# board.net
KiCad netlist of a schematic drawn in EAGLE
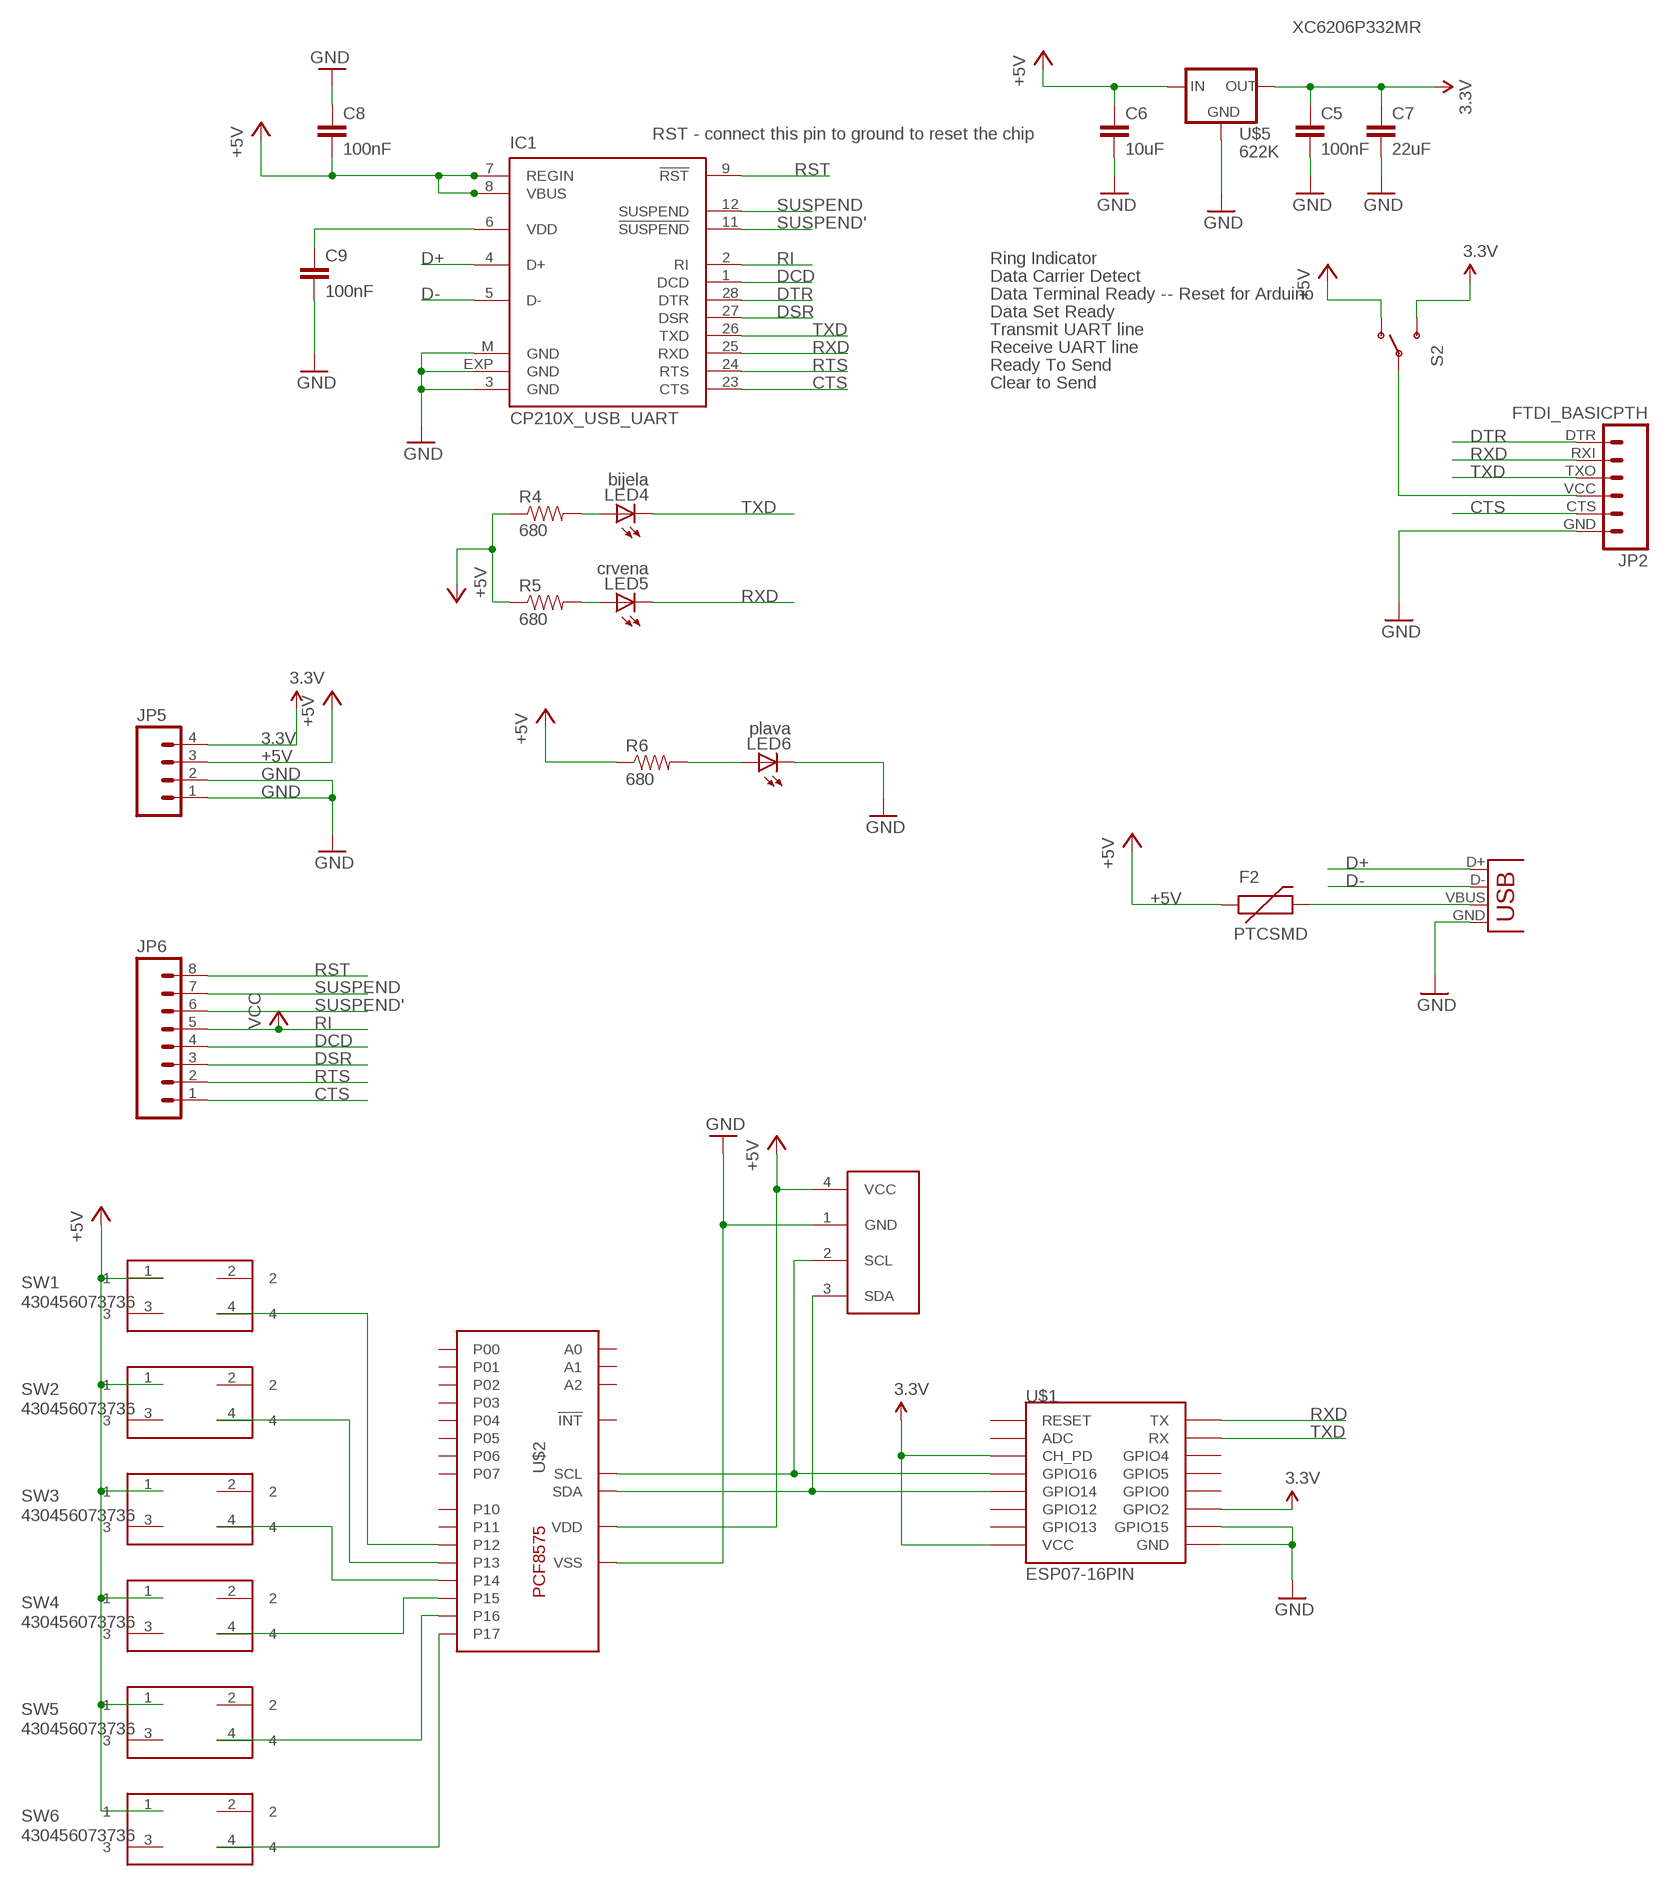
[diagram p0: schematic, sheet 1]

(export (version "E")
  (design (tool "Eeschema 10.0.6"))
  (components
    (comp (ref "C5")
      (value "100nF")
      (footprint "eagle-import:0603-CAP")
      (libsource (lib "eagle-import") (part "CAP0603-CAP"))
    )
    (comp (ref "C6")
      (value "10uF")
      (footprint "eagle-import:C3216")
      (libsource (lib "eagle-import") (part "C-EUC3216"))
    )
    (comp (ref "C7")
      (value "22uF")
      (footprint "eagle-import:C3216")
      (libsource (lib "eagle-import") (part "C-EUC3216"))
    )
    (comp (ref "C8")
      (value "100nF")
      (footprint "eagle-import:0603-CAP")
      (libsource (lib "eagle-import") (part "CAP0603-CAP"))
    )
    (comp (ref "C9")
      (value "100nF")
      (footprint "eagle-import:0603-CAP")
      (libsource (lib "eagle-import") (part "CAP0603-CAP"))
    )
    (comp (ref "F2")
      (value "PTCSMD")
      (footprint "eagle-import:PTC-1206")
      (libsource (lib "eagle-import") (part "PTCSMD"))
    )
    (comp (ref "IC1")
      (value "CP210X_USB_UART")
      (footprint "eagle-import:MLP28")
      (libsource (lib "eagle-import") (part "CP210X_USB_UART"))
    )
    (comp (ref "JP2")
      (value "FTDI_BASICPTH")
      (footprint "eagle-import:FTDI_BASIC")
      (libsource (lib "eagle-import") (part "FTDI_BASICPTH"))
    )
    (comp (ref "JP5")
      (value "M04PTH")
      (footprint "eagle-import:1X04")
      (libsource (lib "eagle-import") (part "M04PTH"))
    )
    (comp (ref "JP6")
      (value "M081X08")
      (footprint "eagle-import:1X08")
      (libsource (lib "eagle-import") (part "M081X08"))
    )
    (comp (ref "LED4")
      (value "bijela")
      (footprint "eagle-import:CHIP-LED0805")
      (libsource (lib "eagle-import") (part "LEDCHIP-LED0805"))
    )
    (comp (ref "LED5")
      (value "crvena")
      (footprint "eagle-import:CHIP-LED0805")
      (libsource (lib "eagle-import") (part "LEDCHIP-LED0805"))
    )
    (comp (ref "LED6")
      (value "plava")
      (footprint "eagle-import:CHIP-LED0805")
      (libsource (lib "eagle-import") (part "LEDCHIP-LED0805"))
    )
    (comp (ref "R4")
      (value "680")
      (footprint "eagle-import:0603-RES")
      (libsource (lib "eagle-import") (part "RESISTOR0603-RES"))
    )
    (comp (ref "R5")
      (value "680")
      (footprint "eagle-import:0603-RES")
      (libsource (lib "eagle-import") (part "RESISTOR0603-RES"))
    )
    (comp (ref "R6")
      (value "680")
      (footprint "eagle-import:0603-RES")
      (libsource (lib "eagle-import") (part "RESISTOR0603-RES"))
    )
    (comp (ref "S2")
      (value "SWITCH-SPST-SMD-A")
      (footprint "eagle-import:SWITCH-SPST-SMD-A")
      (libsource (lib "eagle-import") (part "SWITCH-SPST-SMD-A"))
    )
    (comp (ref "SW1")
      (value "430456073736")
      (footprint "eagle-import:430456073736")
      (libsource (lib "eagle-import") (part "430456073736"))
    )
    (comp (ref "SW2")
      (value "430456073736")
      (footprint "eagle-import:430456073736")
      (libsource (lib "eagle-import") (part "430456073736"))
    )
    (comp (ref "SW3")
      (value "430456073736")
      (footprint "eagle-import:430456073736")
      (libsource (lib "eagle-import") (part "430456073736"))
    )
    (comp (ref "SW4")
      (value "430456073736")
      (footprint "eagle-import:430456073736")
      (libsource (lib "eagle-import") (part "430456073736"))
    )
    (comp (ref "SW5")
      (value "430456073736")
      (footprint "eagle-import:430456073736")
      (libsource (lib "eagle-import") (part "430456073736"))
    )
    (comp (ref "SW6")
      (value "430456073736")
      (footprint "eagle-import:430456073736")
      (libsource (lib "eagle-import") (part "430456073736"))
    )
    (comp (ref "U$1")
      (value "ESP07-16PIN")
      (footprint "eagle-import:ESP07-16PIN")
      (libsource (lib "eagle-import") (part "ESP07-16PIN"))
    )
    (comp (ref "U$2")
      (value "PCF8575C")
      (footprint "eagle-import:SOP24")
      (libsource (lib "eagle-import") (part "PCF8575C"))
    )
    (comp (ref "U$3")
      (value "I2C_OLED")
      (footprint "eagle-import:I2C_OLED_PACKAGE")
      (libsource (lib "eagle-import") (part "I2C_OLED"))
    )
    (comp (ref "U$5")
      (value "622K")
      (footprint "eagle-import:662K")
      (libsource (lib "eagle-import") (part "622K"))
    )
    (comp (ref "X2")
      (value "USB-MICROB")
      (footprint "eagle-import:USB-MICROB")
      (libsource (lib "eagle-import") (part "USB-MICROB"))
    )
  )
  (nets
    (net (code "1") (name "+5V") (class "Default")
      (node (ref "C6") (pin "1") (pinfunction "1_1") (pintype "passive"))
      (node (ref "C8") (pin "2") (pinfunction "2_2") (pintype "passive"))
      (node (ref "F2") (pin "1") (pinfunction "1_1") (pintype "bidirectional"))
      (node (ref "IC1") (pin "7") (pinfunction "REGIN_7") (pintype "passive"))
      (node (ref "IC1") (pin "8") (pinfunction "VBUS_8") (pintype "input"))
      (node (ref "JP5") (pin "3") (pinfunction "3_3") (pintype "passive"))
      (node (ref "R4") (pin "1") (pinfunction "1_1") (pintype "passive"))
      (node (ref "R5") (pin "1") (pinfunction "1_1") (pintype "passive"))
      (node (ref "R6") (pin "1") (pinfunction "1_1") (pintype "passive"))
      (node (ref "S2") (pin "1") (pinfunction "O_1") (pintype "passive"))
      (node (ref "SW1") (pin "1") (pinfunction "1_1") (pintype "bidirectional"))
      (node (ref "SW2") (pin "1") (pinfunction "1_1") (pintype "bidirectional"))
      (node (ref "SW3") (pin "1") (pinfunction "1_1") (pintype "bidirectional"))
      (node (ref "SW4") (pin "1") (pinfunction "1_1") (pintype "bidirectional"))
      (node (ref "SW5") (pin "1") (pinfunction "1_1") (pintype "bidirectional"))
      (node (ref "SW6") (pin "1") (pinfunction "1_1") (pintype "bidirectional"))
      (node (ref "U$2") (pin "P$24") (pinfunction "VDD_P$24") (pintype "power_in"))
      (node (ref "U$3") (pin "4") (pinfunction "VCC_4") (pintype "bidirectional"))
      (node (ref "U$5") (pin "IN") (pinfunction "IN_IN") (pintype "input"))
    )
    (net (code "2") (name "/CTS") (class "Default")
      (node (ref "IC1") (pin "23") (pinfunction "CTS_23") (pintype "input"))
      (node (ref "JP2") (pin "CTS") (pinfunction "5_CTS") (pintype "passive"))
      (node (ref "JP6") (pin "1") (pinfunction "1_1") (pintype "passive"))
    )
    (net (code "3") (name "/D+") (class "Default")
      (node (ref "IC1") (pin "4") (pinfunction "D+_4") (pintype "bidirectional"))
      (node (ref "X2") (pin "D+") (pinfunction "D+_D+") (pintype "bidirectional"))
    )
    (net (code "4") (name "/D-") (class "Default")
      (node (ref "IC1") (pin "5") (pinfunction "D-_5") (pintype "bidirectional"))
      (node (ref "X2") (pin "D-") (pinfunction "D-_D-") (pintype "bidirectional"))
    )
    (net (code "5") (name "/DCD") (class "Default")
      (node (ref "IC1") (pin "1") (pinfunction "DCD_1") (pintype "input"))
      (node (ref "JP6") (pin "4") (pinfunction "4_4") (pintype "passive"))
    )
    (net (code "6") (name "/DSR") (class "Default")
      (node (ref "IC1") (pin "27") (pinfunction "DSR_27") (pintype "input"))
      (node (ref "JP6") (pin "3") (pinfunction "3_3") (pintype "passive"))
    )
    (net (code "7") (name "/DTR") (class "Default")
      (node (ref "IC1") (pin "28") (pinfunction "DTR_28") (pintype "output"))
      (node (ref "JP2") (pin "DTR") (pinfunction "1_DTR") (pintype "passive"))
    )
    (net (code "8") (name "/RST") (class "Default")
      (node (ref "IC1") (pin "9") (pinfunction "~{RST}_9") (pintype "bidirectional"))
      (node (ref "JP6") (pin "8") (pinfunction "8_8") (pintype "passive"))
    )
    (net (code "9") (name "/RTS") (class "Default")
      (node (ref "IC1") (pin "24") (pinfunction "RTS_24") (pintype "output"))
      (node (ref "JP6") (pin "2") (pinfunction "2_2") (pintype "passive"))
    )
    (net (code "10") (name "/RXD") (class "Default")
      (node (ref "IC1") (pin "25") (pinfunction "RXD_25") (pintype "input"))
      (node (ref "JP2") (pin "RXI") (pinfunction "2_RXI") (pintype "passive"))
      (node (ref "LED5") (pin "C") (pinfunction "C_C") (pintype "passive"))
      (node (ref "U$1") (pin "TX") (pinfunction "TX_TX") (pintype "bidirectional"))
    )
    (net (code "11") (name "/SUSPEND") (class "Default")
      (node (ref "IC1") (pin "12") (pinfunction "SUSPEND_12") (pintype "output"))
      (node (ref "JP6") (pin "7") (pinfunction "7_7") (pintype "passive"))
    )
    (net (code "12") (name "/SUSPEND'") (class "Default")
      (node (ref "IC1") (pin "11") (pinfunction "~{SUSPEND}_11") (pintype "output"))
      (node (ref "JP6") (pin "6") (pinfunction "6_6") (pintype "passive"))
    )
    (net (code "13") (name "/TXD") (class "Default")
      (node (ref "IC1") (pin "26") (pinfunction "TXD_26") (pintype "output"))
      (node (ref "JP2") (pin "TXO") (pinfunction "3_TXO") (pintype "passive"))
      (node (ref "LED4") (pin "C") (pinfunction "C_C") (pintype "passive"))
      (node (ref "U$1") (pin "RX") (pinfunction "RX_RX") (pintype "bidirectional"))
    )
    (net (code "14") (name "3.3V") (class "Default")
      (node (ref "C5") (pin "1") (pinfunction "1_1") (pintype "passive"))
      (node (ref "C7") (pin "1") (pinfunction "1_1") (pintype "passive"))
      (node (ref "JP5") (pin "4") (pinfunction "4_4") (pintype "passive"))
      (node (ref "S2") (pin "3") (pinfunction "S_3") (pintype "passive"))
      (node (ref "U$1") (pin "CH_PD") (pinfunction "CH_PD_CH_PD") (pintype "bidirectional"))
      (node (ref "U$1") (pin "GPIO2") (pinfunction "GPIO2_GPIO2") (pintype "bidirectional"))
      (node (ref "U$1") (pin "VCC") (pinfunction "VCC_VCC") (pintype "bidirectional"))
      (node (ref "U$5") (pin "OUT") (pinfunction "OUT_OUT") (pintype "output"))
    )
    (net (code "15") (name "GND") (class "Default")
      (node (ref "C5") (pin "2") (pinfunction "2_2") (pintype "passive"))
      (node (ref "C6") (pin "2") (pinfunction "2_2") (pintype "passive"))
      (node (ref "C7") (pin "2") (pinfunction "2_2") (pintype "passive"))
      (node (ref "C8") (pin "1") (pinfunction "1_1") (pintype "passive"))
      (node (ref "C9") (pin "2") (pinfunction "2_2") (pintype "passive"))
      (node (ref "IC1") (pin "3") (pinfunction "GND_3") (pintype "power_in"))
      (node (ref "IC1") (pin "EXP") (pinfunction "GND_EXP") (pintype "power_in"))
      (node (ref "IC1") (pin "M") (pinfunction "GND_M") (pintype "power_in"))
      (node (ref "JP2") (pin "GND") (pinfunction "6_GND") (pintype "passive"))
      (node (ref "JP5") (pin "1") (pinfunction "1_1") (pintype "passive"))
      (node (ref "JP5") (pin "2") (pinfunction "2_2") (pintype "passive"))
      (node (ref "LED6") (pin "C") (pinfunction "C_C") (pintype "passive"))
      (node (ref "U$1") (pin "GND") (pinfunction "GND_GND") (pintype "bidirectional"))
      (node (ref "U$1") (pin "GPIO15") (pinfunction "GPIO15_GPIO15") (pintype "bidirectional"))
      (node (ref "U$2") (pin "P$12") (pinfunction "VSS_P$12") (pintype "power_in"))
      (node (ref "U$3") (pin "1") (pinfunction "GND_1") (pintype "bidirectional"))
      (node (ref "U$5") (pin "GND") (pinfunction "GND_GND") (pintype "input"))
      (node (ref "X2") (pin "GND") (pinfunction "GND_GND") (pintype "bidirectional"))
    )
    (net (code "16") (name "Net-(F2-Pad2)") (class "Default")
      (node (ref "F2") (pin "2") (pinfunction "2_2") (pintype "bidirectional"))
      (node (ref "X2") (pin "VBUS") (pinfunction "VBUS_VBUS") (pintype "bidirectional"))
    )
    (net (code "17") (name "Net-(IC1-VDD)") (class "Default")
      (node (ref "C9") (pin "1") (pinfunction "1_1") (pintype "passive"))
      (node (ref "IC1") (pin "6") (pinfunction "VDD_6") (pintype "power_in"))
    )
    (net (code "18") (name "Net-(JP2-4)") (class "Default")
      (node (ref "JP2") (pin "VCC") (pinfunction "4_VCC") (pintype "passive"))
      (node (ref "S2") (pin "2") (pinfunction "P_2") (pintype "passive"))
    )
    (net (code "19") (name "Net-(LED4-PadA)") (class "Default")
      (node (ref "LED4") (pin "A") (pinfunction "A_A") (pintype "passive"))
      (node (ref "R4") (pin "2") (pinfunction "2_2") (pintype "passive"))
    )
    (net (code "20") (name "Net-(LED5-PadA)") (class "Default")
      (node (ref "LED5") (pin "A") (pinfunction "A_A") (pintype "passive"))
      (node (ref "R5") (pin "2") (pinfunction "2_2") (pintype "passive"))
    )
    (net (code "21") (name "Net-(LED6-PadA)") (class "Default")
      (node (ref "LED6") (pin "A") (pinfunction "A_A") (pintype "passive"))
      (node (ref "R6") (pin "2") (pinfunction "2_2") (pintype "passive"))
    )
    (net (code "22") (name "Net-(U$2-P12)") (class "Default")
      (node (ref "SW1") (pin "4") (pinfunction "4_4") (pintype "bidirectional"))
      (node (ref "U$2") (pin "P$15") (pinfunction "P12_P$15") (pintype "bidirectional"))
    )
    (net (code "23") (name "Net-(U$2-P13)") (class "Default")
      (node (ref "SW2") (pin "4") (pinfunction "4_4") (pintype "bidirectional"))
      (node (ref "U$2") (pin "P$16") (pinfunction "P13_P$16") (pintype "bidirectional"))
    )
    (net (code "24") (name "Net-(U$2-P14)") (class "Default")
      (node (ref "SW3") (pin "4") (pinfunction "4_4") (pintype "bidirectional"))
      (node (ref "U$2") (pin "P$17") (pinfunction "P14_P$17") (pintype "bidirectional"))
    )
    (net (code "25") (name "Net-(U$2-P15)") (class "Default")
      (node (ref "SW4") (pin "4") (pinfunction "4_4") (pintype "bidirectional"))
      (node (ref "U$2") (pin "P$18") (pinfunction "P15_P$18") (pintype "bidirectional"))
    )
    (net (code "26") (name "Net-(U$2-P16)") (class "Default")
      (node (ref "SW5") (pin "4") (pinfunction "4_4") (pintype "bidirectional"))
      (node (ref "U$2") (pin "P$19") (pinfunction "P16_P$19") (pintype "bidirectional"))
    )
    (net (code "27") (name "Net-(U$2-P17)") (class "Default")
      (node (ref "SW6") (pin "4") (pinfunction "4_4") (pintype "bidirectional"))
      (node (ref "U$2") (pin "P$20") (pinfunction "P17_P$20") (pintype "bidirectional"))
    )
    (net (code "28") (name "Net-(U$2-SCL)") (class "Default")
      (node (ref "U$1") (pin "GPIO16") (pinfunction "GPIO16_GPIO16") (pintype "bidirectional"))
      (node (ref "U$2") (pin "P$22") (pinfunction "SCL_P$22") (pintype "input"))
      (node (ref "U$3") (pin "2") (pinfunction "SCL_2") (pintype "bidirectional"))
    )
    (net (code "29") (name "Net-(U$2-SDA)") (class "Default")
      (node (ref "U$1") (pin "GPIO14") (pinfunction "GPIO14_GPIO14") (pintype "bidirectional"))
      (node (ref "U$2") (pin "P$23") (pinfunction "SDA_P$23") (pintype "bidirectional"))
      (node (ref "U$3") (pin "3") (pinfunction "SDA_3") (pintype "bidirectional"))
    )
    (net (code "30") (name "VCC") (class "Default")
      (node (ref "IC1") (pin "2") (pinfunction "RI_2") (pintype "input"))
      (node (ref "JP6") (pin "5") (pinfunction "5_5") (pintype "passive"))
    )
    (net (code "31") (name "unconnected-(SW1-Pad2)") (class "Default")
      (node (ref "SW1") (pin "2") (pinfunction "2_2") (pintype "bidirectional"))
    )
    (net (code "32") (name "unconnected-(SW1-Pad3)") (class "Default")
      (node (ref "SW1") (pin "3") (pinfunction "3_3") (pintype "bidirectional"))
    )
    (net (code "33") (name "unconnected-(SW2-Pad2)") (class "Default")
      (node (ref "SW2") (pin "2") (pinfunction "2_2") (pintype "bidirectional"))
    )
    (net (code "34") (name "unconnected-(SW2-Pad3)") (class "Default")
      (node (ref "SW2") (pin "3") (pinfunction "3_3") (pintype "bidirectional"))
    )
    (net (code "35") (name "unconnected-(SW3-Pad2)") (class "Default")
      (node (ref "SW3") (pin "2") (pinfunction "2_2") (pintype "bidirectional"))
    )
    (net (code "36") (name "unconnected-(SW3-Pad3)") (class "Default")
      (node (ref "SW3") (pin "3") (pinfunction "3_3") (pintype "bidirectional"))
    )
    (net (code "37") (name "unconnected-(SW4-Pad2)") (class "Default")
      (node (ref "SW4") (pin "2") (pinfunction "2_2") (pintype "bidirectional"))
    )
    (net (code "38") (name "unconnected-(SW4-Pad3)") (class "Default")
      (node (ref "SW4") (pin "3") (pinfunction "3_3") (pintype "bidirectional"))
    )
    (net (code "39") (name "unconnected-(SW5-Pad2)") (class "Default")
      (node (ref "SW5") (pin "2") (pinfunction "2_2") (pintype "bidirectional"))
    )
    (net (code "40") (name "unconnected-(SW5-Pad3)") (class "Default")
      (node (ref "SW5") (pin "3") (pinfunction "3_3") (pintype "bidirectional"))
    )
    (net (code "41") (name "unconnected-(SW6-Pad2)") (class "Default")
      (node (ref "SW6") (pin "2") (pinfunction "2_2") (pintype "bidirectional"))
    )
    (net (code "42") (name "unconnected-(SW6-Pad3)") (class "Default")
      (node (ref "SW6") (pin "3") (pinfunction "3_3") (pintype "bidirectional"))
    )
    (net (code "43") (name "unconnected-(U$1-PadADC)") (class "Default")
      (node (ref "U$1") (pin "ADC") (pinfunction "ADC_ADC") (pintype "bidirectional"))
    )
    (net (code "44") (name "unconnected-(U$1-PadGPIO0)") (class "Default")
      (node (ref "U$1") (pin "GPIO0") (pinfunction "GPIO0_GPIO0") (pintype "bidirectional"))
    )
    (net (code "45") (name "unconnected-(U$1-PadGPIO4)") (class "Default")
      (node (ref "U$1") (pin "GPIO4") (pinfunction "GPIO4_GPIO4") (pintype "bidirectional"))
    )
    (net (code "46") (name "unconnected-(U$1-PadGPIO5)") (class "Default")
      (node (ref "U$1") (pin "GPIO5") (pinfunction "GPIO5_GPIO5") (pintype "bidirectional"))
    )
    (net (code "47") (name "unconnected-(U$1-PadGPIO12)") (class "Default")
      (node (ref "U$1") (pin "GPIO12") (pinfunction "GPIO12_GPIO12") (pintype "bidirectional"))
    )
    (net (code "48") (name "unconnected-(U$1-PadGPIO13)") (class "Default")
      (node (ref "U$1") (pin "GPIO13") (pinfunction "GPIO13_GPIO13") (pintype "bidirectional"))
    )
    (net (code "49") (name "unconnected-(U$1-RESET-PadREST)") (class "Default")
      (node (ref "U$1") (pin "REST") (pinfunction "RESET_REST") (pintype "bidirectional"))
    )
    (net (code "50") (name "unconnected-(U$2-A0-PadP$21)") (class "Default")
      (node (ref "U$2") (pin "P$21") (pinfunction "A0_P$21") (pintype "input"))
    )
    (net (code "51") (name "unconnected-(U$2-A1-PadP$2)") (class "Default")
      (node (ref "U$2") (pin "P$2") (pinfunction "A1_P$2") (pintype "input"))
    )
    (net (code "52") (name "unconnected-(U$2-A2-PadP$3)") (class "Default")
      (node (ref "U$2") (pin "P$3") (pinfunction "A2_P$3") (pintype "input"))
    )
    (net (code "53") (name "unconnected-(U$2-P00-PadP$4)") (class "Default")
      (node (ref "U$2") (pin "P$4") (pinfunction "P00_P$4") (pintype "bidirectional"))
    )
    (net (code "54") (name "unconnected-(U$2-P01-PadP$5)") (class "Default")
      (node (ref "U$2") (pin "P$5") (pinfunction "P01_P$5") (pintype "bidirectional"))
    )
    (net (code "55") (name "unconnected-(U$2-P02-PadP$6)") (class "Default")
      (node (ref "U$2") (pin "P$6") (pinfunction "P02_P$6") (pintype "bidirectional"))
    )
    (net (code "56") (name "unconnected-(U$2-P03-PadP$7)") (class "Default")
      (node (ref "U$2") (pin "P$7") (pinfunction "P03_P$7") (pintype "bidirectional"))
    )
    (net (code "57") (name "unconnected-(U$2-P04-PadP$8)") (class "Default")
      (node (ref "U$2") (pin "P$8") (pinfunction "P04_P$8") (pintype "bidirectional"))
    )
    (net (code "58") (name "unconnected-(U$2-P05-PadP$9)") (class "Default")
      (node (ref "U$2") (pin "P$9") (pinfunction "P05_P$9") (pintype "bidirectional"))
    )
    (net (code "59") (name "unconnected-(U$2-P06-PadP$10)") (class "Default")
      (node (ref "U$2") (pin "P$10") (pinfunction "P06_P$10") (pintype "bidirectional"))
    )
    (net (code "60") (name "unconnected-(U$2-P07-PadP$11)") (class "Default")
      (node (ref "U$2") (pin "P$11") (pinfunction "P07_P$11") (pintype "bidirectional"))
    )
    (net (code "61") (name "unconnected-(U$2-P10-PadP$13)") (class "Default")
      (node (ref "U$2") (pin "P$13") (pinfunction "P10_P$13") (pintype "bidirectional"))
    )
    (net (code "62") (name "unconnected-(U$2-P11-PadP$14)") (class "Default")
      (node (ref "U$2") (pin "P$14") (pinfunction "P11_P$14") (pintype "bidirectional"))
    )
    (net (code "63") (name "unconnected-(U$2-~{INT}-PadP$1)") (class "Default")
      (node (ref "U$2") (pin "P$1") (pinfunction "~{INT}_P$1") (pintype "open_collector"))
    )
  )
)
